# AT261A_LDO.net
KiCad netlist of a schematic drawn in EAGLE
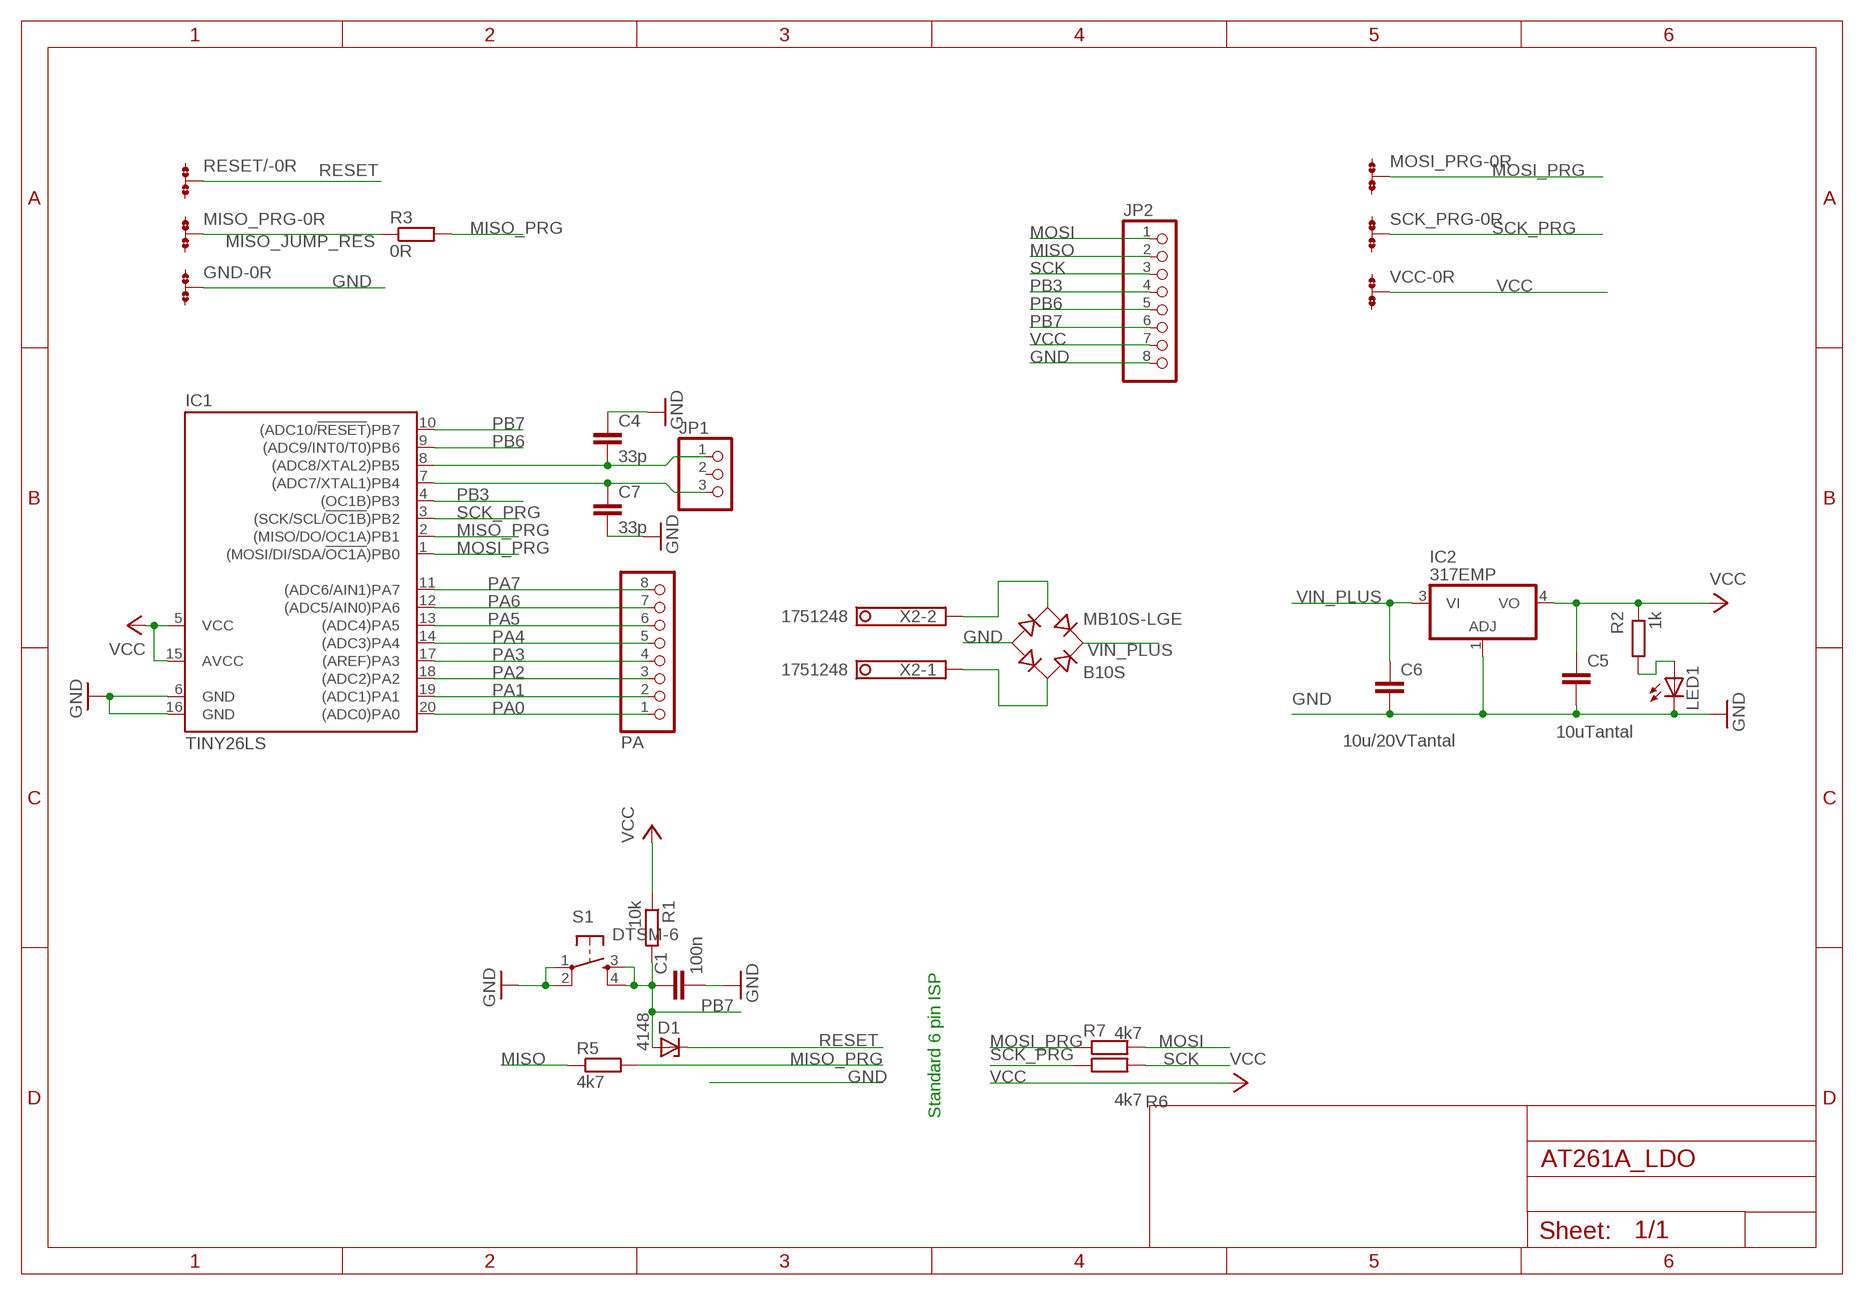
[diagram p0: schematic, sheet 1]

(export (version "E")
  (design (tool "Eeschema 10.0.6"))
  (components
    (comp (ref "C1")
      (value "100n")
      (footprint "eagle-import:C1206")
      (libsource (lib "eagle-import") (part "C-EUC1206"))
    )
    (comp (ref "C4")
      (value "33p")
      (footprint "eagle-import:C1206")
      (libsource (lib "eagle-import") (part "C-EUC1206"))
    )
    (comp (ref "C5")
      (value "10uTantal")
      (footprint "eagle-import:C1206K")
      (libsource (lib "eagle-import") (part "C-EUC1206K"))
    )
    (comp (ref "C6")
      (value "10u/20VTantal")
      (footprint "eagle-import:C1206K")
      (libsource (lib "eagle-import") (part "C-EUC1206K"))
    )
    (comp (ref "C7")
      (value "33p")
      (footprint "eagle-import:C1206")
      (libsource (lib "eagle-import") (part "C-EUC1206"))
    )
    (comp (ref "D1")
      (value "4148")
      (footprint "eagle-import:SMB")
      (libsource (lib "eagle-import") (part "ZENER-DIODESMB"))
    )
    (comp (ref "GND")
      (value "0R-JUMPA")
      (footprint "eagle-import:A0R-JMP")
      (libsource (lib "eagle-import") (part "0R-JUMPA"))
    )
    (comp (ref "IC1")
      (value "TINY26LS")
      (footprint "eagle-import:SO20L")
      (fields (field (name "MPN") "ATTINY26L-8SU"))
      (libsource (lib "eagle-import") (part "TINY26SL"))
    )
    (comp (ref "IC2")
      (value "317EMP")
      (footprint "eagle-import:SOT223")
      (libsource (lib "eagle-import") (part "317EMP"))
    )
    (comp (ref "JP1")
      (value "PINHD-1X3")
      (footprint "eagle-import:1X03")
      (libsource (lib "eagle-import") (part "PINHD-1X3"))
    )
    (comp (ref "JP2")
      (value "PINHD-1X8/90")
      (footprint "eagle-import:1X08_90")
      (libsource (lib "eagle-import") (part "PINHD-1X8/90"))
    )
    (comp (ref "LED1")
      (value "LEDSMT1206")
      (footprint "eagle-import:1206")
      (libsource (lib "eagle-import") (part "LEDSMT1206"))
    )
    (comp (ref "MB10S-LGE")
      (value "B10S")
      (footprint "eagle-import:MBS")
      (libsource (lib "eagle-import") (part "BS10"))
    )
    (comp (ref "MISO_PRG")
      (value "0R-JUMPA")
      (footprint "eagle-import:A0R-JMP")
      (libsource (lib "eagle-import") (part "0R-JUMPA"))
    )
    (comp (ref "MOSI_PRG")
      (value "0R-JUMPA")
      (footprint "eagle-import:A0R-JMP")
      (libsource (lib "eagle-import") (part "0R-JUMPA"))
    )
    (comp (ref "PA")
      (value "PINHD-1X8/90")
      (footprint "eagle-import:1X08_90")
      (libsource (lib "eagle-import") (part "PINHD-1X8/90"))
    )
    (comp (ref "R1")
      (value "10k")
      (footprint "eagle-import:R1206")
      (libsource (lib "eagle-import") (part "R-EU_R1206"))
    )
    (comp (ref "R2")
      (value "1k")
      (footprint "eagle-import:R1206")
      (libsource (lib "eagle-import") (part "resistor_R-EU_R1206"))
    )
    (comp (ref "R3")
      (value "0R")
      (footprint "eagle-import:M1406")
      (libsource (lib "eagle-import") (part "resistor_R-EU_M1406"))
    )
    (comp (ref "R5")
      (value "4k7")
      (footprint "eagle-import:R1206")
      (libsource (lib "eagle-import") (part "R-EU_R1206"))
    )
    (comp (ref "R6")
      (value "4k7")
      (footprint "eagle-import:R1206")
      (libsource (lib "eagle-import") (part "R-EU_R1206"))
    )
    (comp (ref "R7")
      (value "4k7")
      (footprint "eagle-import:R1206")
      (libsource (lib "eagle-import") (part "R-EU_R1206"))
    )
    (comp (ref "RESET/")
      (value "0R-JUMPA")
      (footprint "eagle-import:A0R-JMP")
      (libsource (lib "eagle-import") (part "0R-JUMPA"))
    )
    (comp (ref "S1")
      (value "DTSM-6")
      (footprint "eagle-import:DTSM-6")
      (libsource (lib "eagle-import") (part "DTSM-6"))
    )
    (comp (ref "SCK_PRG")
      (value "0R-JUMPA")
      (footprint "eagle-import:A0R-JMP")
      (libsource (lib "eagle-import") (part "0R-JUMPA"))
    )
    (comp (ref "VCC")
      (value "0R-JUMPA")
      (footprint "eagle-import:A0R-JMP")
      (libsource (lib "eagle-import") (part "0R-JUMPA"))
    )
    (comp (ref "X2")
      (value "1751248")
      (footprint "eagle-import:1751248")
      (libsource (lib "eagle-import") (part "1751248"))
    )
  )
  (nets
    (net (code "1") (name "/MISO") (class "Default")
      (node (ref "JP2") (pin "2") (pinfunction "2_2") (pintype "passive"))
      (node (ref "R5") (pin "1") (pinfunction "1_1") (pintype "passive"))
    )
    (net (code "2") (name "/MISO_JUMP_RES") (class "Default")
      (node (ref "MISO_PRG") (pin "2") (pinfunction "2_2") (pintype "passive"))
      (node (ref "R3") (pin "1") (pinfunction "1_1") (pintype "passive"))
    )
    (net (code "3") (name "/MISO_PRG") (class "Default")
      (node (ref "IC1") (pin "2") (pinfunction "(MISO/DO/OC1A)PB1_2") (pintype "bidirectional"))
      (node (ref "R3") (pin "2") (pinfunction "2_2") (pintype "passive"))
      (node (ref "R5") (pin "2") (pinfunction "2_2") (pintype "passive"))
    )
    (net (code "4") (name "/MOSI") (class "Default")
      (node (ref "JP2") (pin "1") (pinfunction "1_1") (pintype "passive"))
      (node (ref "R7") (pin "2") (pinfunction "2_2") (pintype "passive"))
    )
    (net (code "5") (name "/MOSI_PRG") (class "Default")
      (node (ref "IC1") (pin "1") (pinfunction "(MOSI/DI/SDA/~{OC1A})PB0_1") (pintype "bidirectional"))
      (node (ref "MOSI_PRG") (pin "2") (pinfunction "2_2") (pintype "passive"))
      (node (ref "R7") (pin "1") (pinfunction "1_1") (pintype "passive"))
    )
    (net (code "6") (name "/PA0") (class "Default")
      (node (ref "IC1") (pin "20") (pinfunction "(ADC0)PA0_20") (pintype "bidirectional"))
      (node (ref "PA") (pin "1") (pinfunction "1_1") (pintype "passive"))
    )
    (net (code "7") (name "/PA1") (class "Default")
      (node (ref "IC1") (pin "19") (pinfunction "(ADC1)PA1_19") (pintype "bidirectional"))
      (node (ref "PA") (pin "2") (pinfunction "2_2") (pintype "passive"))
    )
    (net (code "8") (name "/PA2") (class "Default")
      (node (ref "IC1") (pin "18") (pinfunction "(ADC2)PA2_18") (pintype "bidirectional"))
      (node (ref "PA") (pin "3") (pinfunction "3_3") (pintype "passive"))
    )
    (net (code "9") (name "/PA3") (class "Default")
      (node (ref "IC1") (pin "17") (pinfunction "(AREF)PA3_17") (pintype "bidirectional"))
      (node (ref "PA") (pin "4") (pinfunction "4_4") (pintype "passive"))
    )
    (net (code "10") (name "/PA4") (class "Default")
      (node (ref "IC1") (pin "14") (pinfunction "(ADC3)PA4_14") (pintype "bidirectional"))
      (node (ref "PA") (pin "5") (pinfunction "5_5") (pintype "passive"))
    )
    (net (code "11") (name "/PA5") (class "Default")
      (node (ref "IC1") (pin "13") (pinfunction "(ADC4)PA5_13") (pintype "bidirectional"))
      (node (ref "PA") (pin "6") (pinfunction "6_6") (pintype "passive"))
    )
    (net (code "12") (name "/PA6") (class "Default")
      (node (ref "IC1") (pin "12") (pinfunction "(ADC5/AIN0)PA6_12") (pintype "bidirectional"))
      (node (ref "PA") (pin "7") (pinfunction "7_7") (pintype "passive"))
    )
    (net (code "13") (name "/PA7") (class "Default")
      (node (ref "IC1") (pin "11") (pinfunction "(ADC6/AIN1)PA7_11") (pintype "bidirectional"))
      (node (ref "PA") (pin "8") (pinfunction "8_8") (pintype "passive"))
    )
    (net (code "14") (name "/PB3") (class "Default")
      (node (ref "IC1") (pin "4") (pinfunction "(OC1B)PB3_4") (pintype "bidirectional"))
      (node (ref "JP2") (pin "4") (pinfunction "4_4") (pintype "passive"))
    )
    (net (code "15") (name "/PB6") (class "Default")
      (node (ref "IC1") (pin "9") (pinfunction "(ADC9/INT0/T0)PB6_9") (pintype "bidirectional"))
      (node (ref "JP2") (pin "5") (pinfunction "5_5") (pintype "passive"))
    )
    (net (code "16") (name "/PB7") (class "Default")
      (node (ref "C1") (pin "1") (pinfunction "1_1") (pintype "passive"))
      (node (ref "D1") (pin "A") (pinfunction "A_A") (pintype "passive"))
      (node (ref "IC1") (pin "10") (pinfunction "(ADC10/~{RESET})PB7_10") (pintype "bidirectional"))
      (node (ref "JP2") (pin "6") (pinfunction "6_6") (pintype "passive"))
      (node (ref "R1") (pin "2") (pinfunction "2_2") (pintype "passive"))
      (node (ref "S1") (pin "3") (pinfunction "3_3") (pintype "passive"))
      (node (ref "S1") (pin "4") (pinfunction "4_4") (pintype "passive"))
    )
    (net (code "17") (name "/RESET") (class "Default")
      (node (ref "D1") (pin "C") (pinfunction "C_C") (pintype "passive"))
      (node (ref "RESET/") (pin "2") (pinfunction "2_2") (pintype "passive"))
    )
    (net (code "18") (name "/SCK") (class "Default")
      (node (ref "JP2") (pin "3") (pinfunction "3_3") (pintype "passive"))
      (node (ref "R6") (pin "2") (pinfunction "2_2") (pintype "passive"))
    )
    (net (code "19") (name "/SCK_PRG") (class "Default")
      (node (ref "IC1") (pin "3") (pinfunction "(SCK/SCL/~{OC1B})PB2_3") (pintype "bidirectional"))
      (node (ref "R6") (pin "1") (pinfunction "1_1") (pintype "passive"))
      (node (ref "SCK_PRG") (pin "2") (pinfunction "2_2") (pintype "passive"))
    )
    (net (code "20") (name "/VIN_PLUS") (class "Default")
      (node (ref "C6") (pin "1") (pinfunction "1_1") (pintype "passive"))
      (node (ref "IC2") (pin "3") (pinfunction "VI_3") (pintype "input"))
      (node (ref "MB10S-LGE") (pin "+") (pinfunction "+_+") (pintype "passive"))
    )
    (net (code "21") (name "GND") (class "Default")
      (node (ref "C1") (pin "2") (pinfunction "2_2") (pintype "passive"))
      (node (ref "C4") (pin "1") (pinfunction "1_1") (pintype "passive"))
      (node (ref "C5") (pin "2") (pinfunction "2_2") (pintype "passive"))
      (node (ref "C6") (pin "2") (pinfunction "2_2") (pintype "passive"))
      (node (ref "C7") (pin "2") (pinfunction "2_2") (pintype "passive"))
      (node (ref "GND") (pin "2") (pinfunction "2_2") (pintype "passive"))
      (node (ref "IC1") (pin "16") (pinfunction "GND_16") (pintype "power_in"))
      (node (ref "IC1") (pin "6") (pinfunction "GND_6") (pintype "power_in"))
      (node (ref "IC2") (pin "1") (pinfunction "ADJ_1") (pintype "input"))
      (node (ref "JP2") (pin "8") (pinfunction "8_8") (pintype "passive"))
      (node (ref "LED1") (pin "C") (pinfunction "C_C") (pintype "passive"))
      (node (ref "MB10S-LGE") (pin "-") (pinfunction "-_-") (pintype "passive"))
      (node (ref "S1") (pin "1") (pinfunction "1_1") (pintype "passive"))
      (node (ref "S1") (pin "2") (pinfunction "2_2") (pintype "passive"))
    )
    (net (code "22") (name "Net-(IC1-(ADC7{slash}XTAL1)PB4)") (class "Default")
      (node (ref "C7") (pin "1") (pinfunction "1_1") (pintype "passive"))
      (node (ref "IC1") (pin "7") (pinfunction "(ADC7/XTAL1)PB4_7") (pintype "bidirectional"))
      (node (ref "JP1") (pin "3") (pinfunction "3_3") (pintype "passive"))
    )
    (net (code "23") (name "Net-(IC1-(ADC8{slash}XTAL2)PB5)") (class "Default")
      (node (ref "C4") (pin "2") (pinfunction "2_2") (pintype "passive"))
      (node (ref "IC1") (pin "8") (pinfunction "(ADC8/XTAL2)PB5_8") (pintype "bidirectional"))
      (node (ref "JP1") (pin "1") (pinfunction "1_1") (pintype "passive"))
    )
    (net (code "24") (name "Net-(LED1-PadA)") (class "Default")
      (node (ref "LED1") (pin "A") (pinfunction "A_A") (pintype "passive"))
      (node (ref "R2") (pin "1") (pinfunction "1_1") (pintype "passive"))
    )
    (net (code "25") (name "Net-(X2A-K)") (class "Default")
      (node (ref "MB10S-LGE") (pin "AC2") (pinfunction "AC2_AC2") (pintype "passive"))
      (node (ref "X2") (pin "1") (pinfunction "K_1") (pintype "passive"))
    )
    (net (code "26") (name "Net-(X2B-K)") (class "Default")
      (node (ref "MB10S-LGE") (pin "AC1") (pinfunction "AC1_AC1") (pintype "passive"))
      (node (ref "X2") (pin "2") (pinfunction "K_2") (pintype "passive"))
    )
    (net (code "27") (name "VCC") (class "Default")
      (node (ref "C5") (pin "1") (pinfunction "1_1") (pintype "passive"))
      (node (ref "IC1") (pin "15") (pinfunction "AVCC_15") (pintype "power_in"))
      (node (ref "IC1") (pin "5") (pinfunction "VCC_5") (pintype "power_in"))
      (node (ref "IC2") (pin "4") (pinfunction "VO_4") (pintype "passive"))
      (node (ref "JP2") (pin "7") (pinfunction "7_7") (pintype "passive"))
      (node (ref "R1") (pin "1") (pinfunction "1_1") (pintype "passive"))
      (node (ref "R2") (pin "2") (pinfunction "2_2") (pintype "passive"))
      (node (ref "VCC") (pin "2") (pinfunction "2_2") (pintype "passive"))
    )
    (net (code "28") (name "unconnected-(GND-Pad1)") (class "Default")
      (node (ref "GND") (pin "1") (pinfunction "1_1") (pintype "passive"))
    )
    (net (code "29") (name "unconnected-(GND-Pad3)") (class "Default")
      (node (ref "GND") (pin "3") (pinfunction "3_3") (pintype "passive"))
    )
    (net (code "30") (name "unconnected-(JP1-Pad2)") (class "Default")
      (node (ref "JP1") (pin "2") (pinfunction "2_2") (pintype "passive"))
    )
    (net (code "31") (name "unconnected-(MISO_PRG-Pad1)") (class "Default")
      (node (ref "MISO_PRG") (pin "1") (pinfunction "1_1") (pintype "passive"))
    )
    (net (code "32") (name "unconnected-(MISO_PRG-Pad3)") (class "Default")
      (node (ref "MISO_PRG") (pin "3") (pinfunction "3_3") (pintype "passive"))
    )
    (net (code "33") (name "unconnected-(MOSI_PRG-Pad1)") (class "Default")
      (node (ref "MOSI_PRG") (pin "1") (pinfunction "1_1") (pintype "passive"))
    )
    (net (code "34") (name "unconnected-(MOSI_PRG-Pad3)") (class "Default")
      (node (ref "MOSI_PRG") (pin "3") (pinfunction "3_3") (pintype "passive"))
    )
    (net (code "35") (name "unconnected-(RESET/-Pad1)") (class "Default")
      (node (ref "RESET/") (pin "1") (pinfunction "1_1") (pintype "passive"))
    )
    (net (code "36") (name "unconnected-(RESET/-Pad3)") (class "Default")
      (node (ref "RESET/") (pin "3") (pinfunction "3_3") (pintype "passive"))
    )
    (net (code "37") (name "unconnected-(SCK_PRG-Pad1)") (class "Default")
      (node (ref "SCK_PRG") (pin "1") (pinfunction "1_1") (pintype "passive"))
    )
    (net (code "38") (name "unconnected-(SCK_PRG-Pad3)") (class "Default")
      (node (ref "SCK_PRG") (pin "3") (pinfunction "3_3") (pintype "passive"))
    )
    (net (code "39") (name "unconnected-(VCC-Pad1)") (class "Default")
      (node (ref "VCC") (pin "1") (pinfunction "1_1") (pintype "passive"))
    )
    (net (code "40") (name "unconnected-(VCC-Pad3)") (class "Default")
      (node (ref "VCC") (pin "3") (pinfunction "3_3") (pintype "passive"))
    )
  )
)
